# Xduino7_0.net
KiCad netlist of a schematic drawn in EAGLE
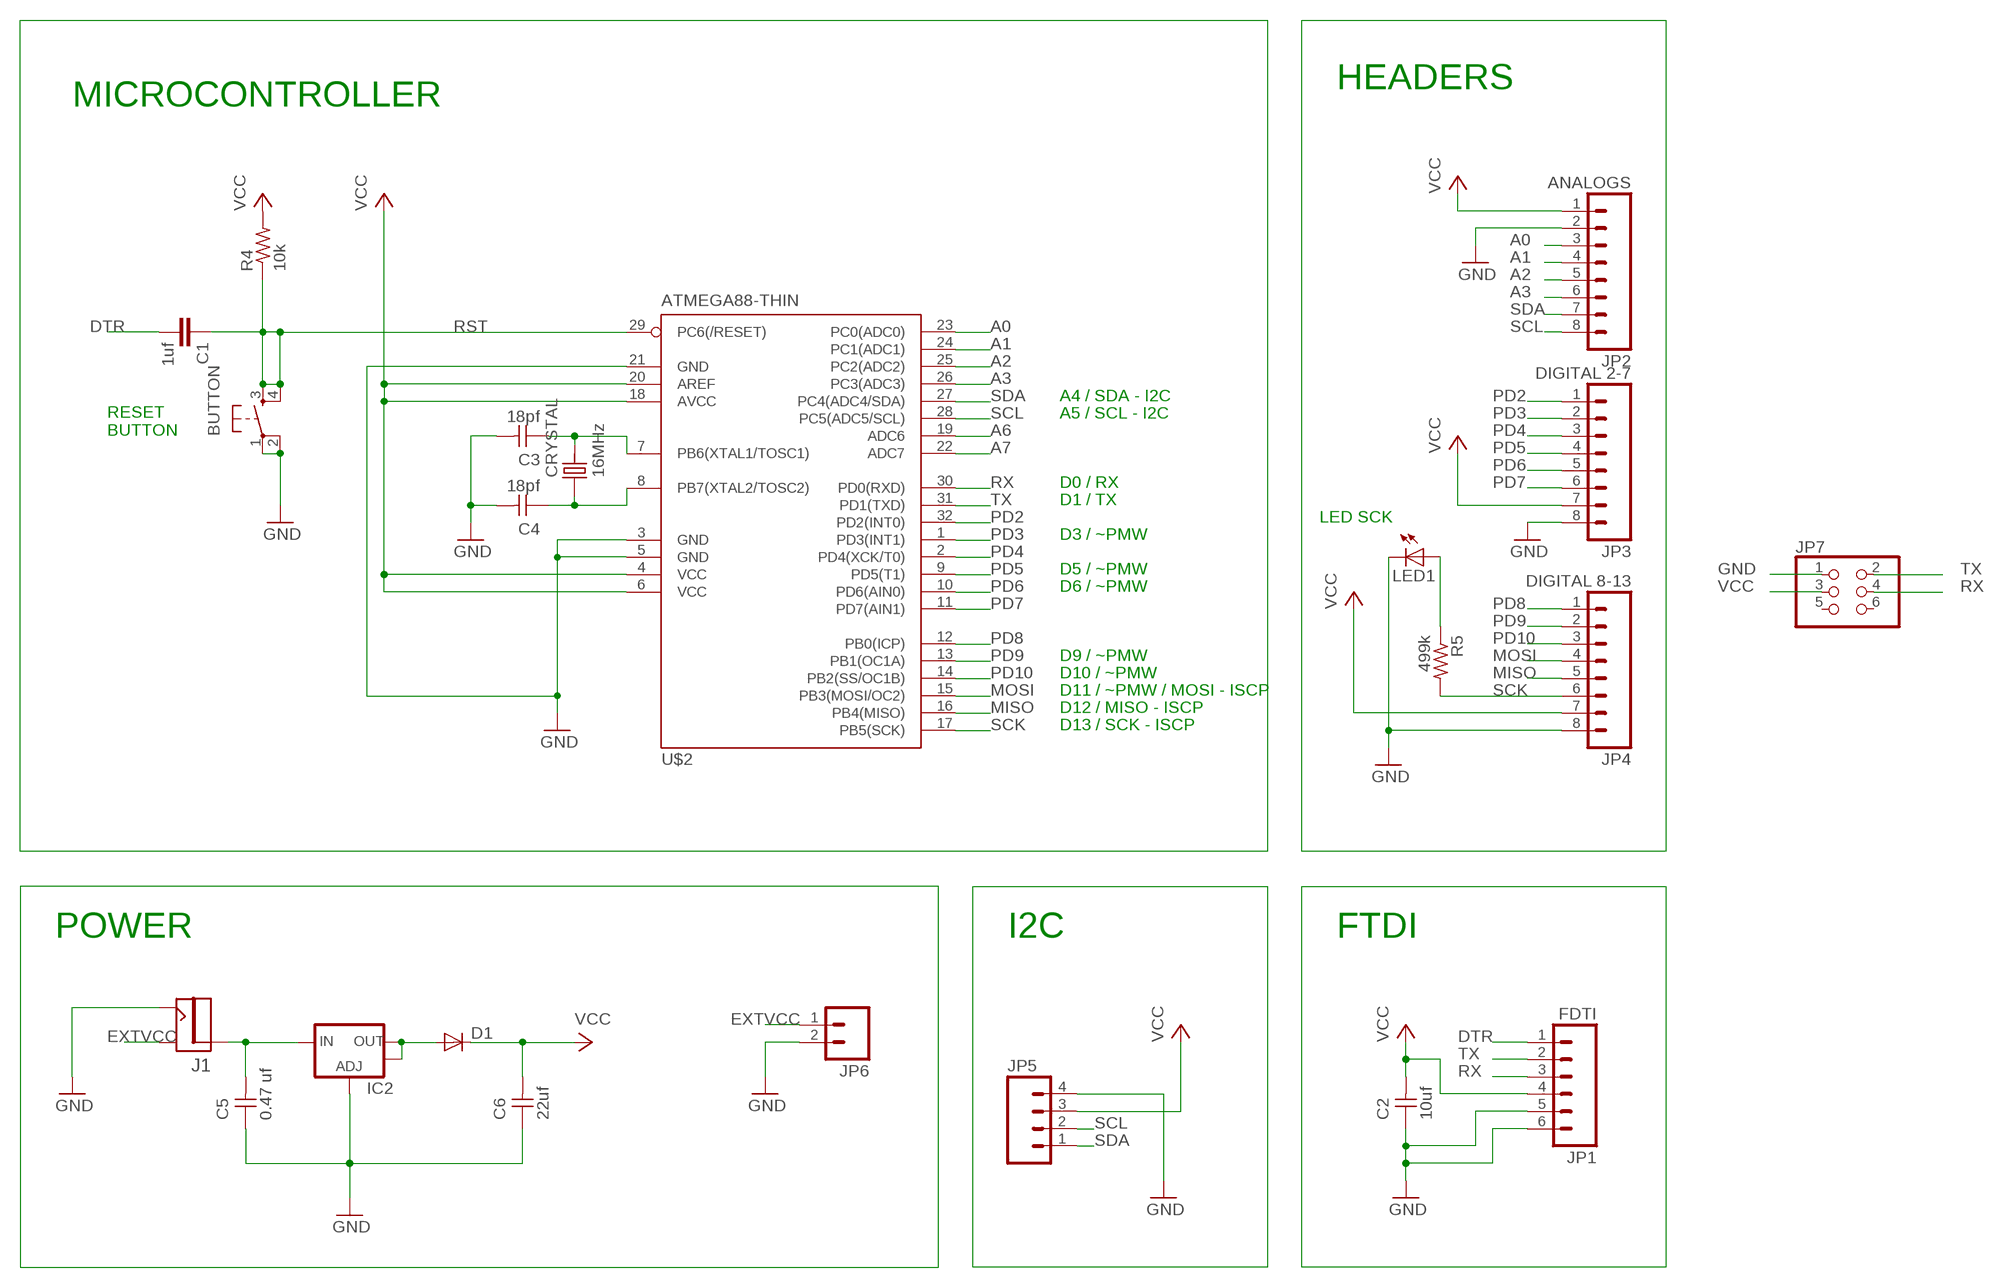
[diagram p0: schematic, sheet 1]

(export (version "E")
  (design (tool "Eeschema 10.0.6"))
  (components
    (comp (ref "BUTTON")
      (value "6MM_SWITCH6MM_SWITCH")
      (footprint "eagle-import:6MM_SWITCH")
      (libsource (lib "eagle-import") (part "6MM_SWITCH6MM_SWITCH"))
    )
    (comp (ref "C1")
      (value "1uf")
      (footprint "eagle-import:1206")
      (libsource (lib "eagle-import") (part "CAP1206"))
    )
    (comp (ref "C2")
      (value "10uf")
      (footprint "eagle-import:1206")
      (libsource (lib "eagle-import") (part "UNPOLARIZED_CAPACITOR1206"))
    )
    (comp (ref "C3")
      (value "18pf")
      (footprint "eagle-import:1206")
      (libsource (lib "eagle-import") (part "UNPOLARIZED_CAPACITOR1206"))
    )
    (comp (ref "C4")
      (value "18pf")
      (footprint "eagle-import:1206")
      (libsource (lib "eagle-import") (part "UNPOLARIZED_CAPACITOR1206"))
    )
    (comp (ref "C5")
      (value "0.47 uf")
      (footprint "eagle-import:1206")
      (libsource (lib "eagle-import") (part "UNPOLARIZED_CAPACITOR1206"))
    )
    (comp (ref "C6")
      (value "22uf")
      (footprint "eagle-import:1206")
      (libsource (lib "eagle-import") (part "UNPOLARIZED_CAPACITOR1206"))
    )
    (comp (ref "CRYSTAL")
      (value "16MHz")
      (footprint "eagle-import:CS10")
      (libsource (lib "eagle-import") (part "CRYSTALCS10"))
    )
    (comp (ref "D1")
      (value "DIODESOD123")
      (footprint "eagle-import:SOD123")
      (libsource (lib "eagle-import") (part "DIODESOD123"))
    )
    (comp (ref "IC2")
      (value "V_REG_LM1117SOT223")
      (footprint "eagle-import:SOT223")
      (libsource (lib "eagle-import") (part "V_REG_LM1117SOT223"))
    )
    (comp (ref "J1")
      (value "JACK.65MM")
      (footprint "eagle-import:JACK_.65MM")
      (libsource (lib "eagle-import") (part "JACK.65MM"))
    )
    (comp (ref "JP1")
      (value "FDTI")
      (footprint "eagle-import:1X06-SMD_EDGE")
      (libsource (lib "eagle-import") (part "M061X06-SMD_EDGE_FEMALE"))
    )
    (comp (ref "JP2")
      (value "ANALOGS")
      (footprint "eagle-import:1X08")
      (libsource (lib "eagle-import") (part "M08"))
    )
    (comp (ref "JP3")
      (value "DIGITAL 2-7")
      (footprint "eagle-import:1X08")
      (libsource (lib "eagle-import") (part "M08"))
    )
    (comp (ref "JP4")
      (value "DIGITAL 8-13")
      (footprint "eagle-import:1X08")
      (libsource (lib "eagle-import") (part "M08"))
    )
    (comp (ref "JP5")
      (value "M04PTH")
      (footprint "eagle-import:1X04")
      (libsource (lib "eagle-import") (part "M04PTH"))
    )
    (comp (ref "JP6")
      (value "M02PTH")
      (footprint "eagle-import:1X02")
      (libsource (lib "eagle-import") (part "M02PTH"))
    )
    (comp (ref "JP7")
      (value "PINHD-2X3-SMD")
      (footprint "eagle-import:2X03SMD")
      (libsource (lib "eagle-import") (part "PINHD-2X3-SMD"))
    )
    (comp (ref "LED1")
      (value "LED1206")
      (footprint "eagle-import:1206")
      (libsource (lib "eagle-import") (part "LED1206"))
    )
    (comp (ref "R4")
      (value "10k")
      (footprint "eagle-import:1206")
      (libsource (lib "eagle-import") (part "RESISTOR1206"))
    )
    (comp (ref "R5")
      (value "499k")
      (footprint "eagle-import:1206")
      (libsource (lib "eagle-import") (part "01_ng_RESISTOR1206"))
    )
    (comp (ref "U$2")
      (value "ATMEGA88-THIN")
      (footprint "eagle-import:TQFP32-08THIN")
      (libsource (lib "eagle-import") (part "ATMEGA88-THIN"))
    )
  )
  (nets
    (net (code "1") (name "/A0") (class "Default")
      (node (ref "JP2") (pin "3") (pinfunction "3_3") (pintype "passive"))
      (node (ref "U$2") (pin "23") (pinfunction "PC0(ADC0)_23") (pintype "bidirectional"))
    )
    (net (code "2") (name "/A1") (class "Default")
      (node (ref "JP2") (pin "4") (pinfunction "4_4") (pintype "passive"))
      (node (ref "U$2") (pin "24") (pinfunction "PC1(ADC1)_24") (pintype "bidirectional"))
    )
    (net (code "3") (name "/A2") (class "Default")
      (node (ref "JP2") (pin "5") (pinfunction "5_5") (pintype "passive"))
      (node (ref "U$2") (pin "25") (pinfunction "PC2(ADC2)_25") (pintype "bidirectional"))
    )
    (net (code "4") (name "/A3") (class "Default")
      (node (ref "JP2") (pin "6") (pinfunction "6_6") (pintype "passive"))
      (node (ref "U$2") (pin "26") (pinfunction "PC3(ADC3)_26") (pintype "bidirectional"))
    )
    (net (code "5") (name "/A6") (class "Default")
      (node (ref "U$2") (pin "19") (pinfunction "ADC6_19") (pintype "bidirectional"))
    )
    (net (code "6") (name "/A7") (class "Default")
      (node (ref "U$2") (pin "22") (pinfunction "ADC7_22") (pintype "bidirectional"))
    )
    (net (code "7") (name "/DTR") (class "Default")
      (node (ref "C1") (pin "2") (pinfunction "2_2") (pintype "passive"))
      (node (ref "JP1") (pin "1") (pinfunction "1_1") (pintype "passive"))
    )
    (net (code "8") (name "/EXTVCC") (class "Default")
      (node (ref "J1") (pin "CONTACT") (pinfunction "SHUNT_CONTACT") (pintype "bidirectional"))
      (node (ref "JP6") (pin "1") (pinfunction "1_1") (pintype "passive"))
    )
    (net (code "9") (name "/MISO") (class "Default")
      (node (ref "JP4") (pin "5") (pinfunction "5_5") (pintype "passive"))
      (node (ref "U$2") (pin "16") (pinfunction "PB4(MISO)_16") (pintype "bidirectional"))
    )
    (net (code "10") (name "/MOSI") (class "Default")
      (node (ref "JP4") (pin "4") (pinfunction "4_4") (pintype "passive"))
      (node (ref "U$2") (pin "15") (pinfunction "PB3(MOSI/OC2)_15") (pintype "bidirectional"))
    )
    (net (code "11") (name "/PD2") (class "Default")
      (node (ref "JP3") (pin "1") (pinfunction "1_1") (pintype "passive"))
      (node (ref "U$2") (pin "32") (pinfunction "PD2(INT0)_32") (pintype "bidirectional"))
    )
    (net (code "12") (name "/PD3") (class "Default")
      (node (ref "JP3") (pin "2") (pinfunction "2_2") (pintype "passive"))
      (node (ref "U$2") (pin "1") (pinfunction "PD3(INT1)_1") (pintype "bidirectional"))
    )
    (net (code "13") (name "/PD4") (class "Default")
      (node (ref "JP3") (pin "3") (pinfunction "3_3") (pintype "passive"))
      (node (ref "U$2") (pin "2") (pinfunction "PD4(XCK/T0)_2") (pintype "bidirectional"))
    )
    (net (code "14") (name "/PD5") (class "Default")
      (node (ref "JP3") (pin "4") (pinfunction "4_4") (pintype "passive"))
      (node (ref "U$2") (pin "9") (pinfunction "PD5(T1)_9") (pintype "bidirectional"))
    )
    (net (code "15") (name "/PD6") (class "Default")
      (node (ref "JP3") (pin "5") (pinfunction "5_5") (pintype "passive"))
      (node (ref "U$2") (pin "10") (pinfunction "PD6(AIN0)_10") (pintype "bidirectional"))
    )
    (net (code "16") (name "/PD7") (class "Default")
      (node (ref "JP3") (pin "6") (pinfunction "6_6") (pintype "passive"))
      (node (ref "U$2") (pin "11") (pinfunction "PD7(AIN1)_11") (pintype "bidirectional"))
    )
    (net (code "17") (name "/PD8") (class "Default")
      (node (ref "JP4") (pin "1") (pinfunction "1_1") (pintype "passive"))
      (node (ref "U$2") (pin "12") (pinfunction "PB0(ICP)_12") (pintype "bidirectional"))
    )
    (net (code "18") (name "/PD9") (class "Default")
      (node (ref "JP4") (pin "2") (pinfunction "2_2") (pintype "passive"))
      (node (ref "U$2") (pin "13") (pinfunction "PB1(OC1A)_13") (pintype "bidirectional"))
    )
    (net (code "19") (name "/PD10") (class "Default")
      (node (ref "JP4") (pin "3") (pinfunction "3_3") (pintype "passive"))
      (node (ref "U$2") (pin "14") (pinfunction "PB2(SS/OC1B)_14") (pintype "bidirectional"))
    )
    (net (code "20") (name "/RST") (class "Default")
      (node (ref "BUTTON") (pin "3") (pinfunction "S_3") (pintype "passive"))
      (node (ref "BUTTON") (pin "4") (pinfunction "S1_4") (pintype "passive"))
      (node (ref "C1") (pin "1") (pinfunction "1_1") (pintype "passive"))
      (node (ref "R4") (pin "1") (pinfunction "1_1") (pintype "passive"))
      (node (ref "U$2") (pin "29") (pinfunction "PC6(/RESET)_29") (pintype "bidirectional"))
    )
    (net (code "21") (name "/RX") (class "Default")
      (node (ref "JP1") (pin "3") (pinfunction "3_3") (pintype "passive"))
      (node (ref "JP7") (pin "4") (pinfunction "4_4") (pintype "passive"))
      (node (ref "U$2") (pin "30") (pinfunction "PD0(RXD)_30") (pintype "bidirectional"))
    )
    (net (code "22") (name "/SCK") (class "Default")
      (node (ref "JP4") (pin "6") (pinfunction "6_6") (pintype "passive"))
      (node (ref "R5") (pin "2") (pinfunction "2_2") (pintype "passive"))
      (node (ref "U$2") (pin "17") (pinfunction "PB5(SCK)_17") (pintype "bidirectional"))
    )
    (net (code "23") (name "/SCL") (class "Default")
      (node (ref "JP2") (pin "8") (pinfunction "8_8") (pintype "passive"))
      (node (ref "JP5") (pin "2") (pinfunction "2_2") (pintype "passive"))
      (node (ref "U$2") (pin "28") (pinfunction "PC5(ADC5/SCL)_28") (pintype "bidirectional"))
    )
    (net (code "24") (name "/SDA") (class "Default")
      (node (ref "JP2") (pin "7") (pinfunction "7_7") (pintype "passive"))
      (node (ref "JP5") (pin "1") (pinfunction "1_1") (pintype "passive"))
      (node (ref "U$2") (pin "27") (pinfunction "PC4(ADC4/SDA)_27") (pintype "bidirectional"))
    )
    (net (code "25") (name "/TX") (class "Default")
      (node (ref "JP1") (pin "2") (pinfunction "2_2") (pintype "passive"))
      (node (ref "JP7") (pin "2") (pinfunction "2_2") (pintype "passive"))
      (node (ref "U$2") (pin "31") (pinfunction "PD1(TXD)_31") (pintype "bidirectional"))
    )
    (net (code "26") (name "GND") (class "Default")
      (node (ref "BUTTON") (pin "1") (pinfunction "P_1") (pintype "passive"))
      (node (ref "BUTTON") (pin "2") (pinfunction "P1_2") (pintype "passive"))
      (node (ref "C2") (pin "1") (pinfunction "1_1") (pintype "passive"))
      (node (ref "C3") (pin "2") (pinfunction "2_2") (pintype "passive"))
      (node (ref "C4") (pin "2") (pinfunction "2_2") (pintype "passive"))
      (node (ref "C5") (pin "1") (pinfunction "1_1") (pintype "passive"))
      (node (ref "C6") (pin "1") (pinfunction "1_1") (pintype "passive"))
      (node (ref "IC2") (pin "1") (pinfunction "ADJ_1") (pintype "input"))
      (node (ref "J1") (pin "SHUNT") (pinfunction "CONTACT_SHUNT") (pintype "bidirectional"))
      (node (ref "JP1") (pin "5") (pinfunction "5_5") (pintype "passive"))
      (node (ref "JP1") (pin "6") (pinfunction "6_6") (pintype "passive"))
      (node (ref "JP2") (pin "2") (pinfunction "2_2") (pintype "passive"))
      (node (ref "JP3") (pin "8") (pinfunction "8_8") (pintype "passive"))
      (node (ref "JP4") (pin "8") (pinfunction "8_8") (pintype "passive"))
      (node (ref "JP5") (pin "4") (pinfunction "4_4") (pintype "passive"))
      (node (ref "JP6") (pin "2") (pinfunction "2_2") (pintype "passive"))
      (node (ref "JP7") (pin "1") (pinfunction "1_1") (pintype "passive"))
      (node (ref "LED1") (pin "2") (pinfunction "C_2") (pintype "passive"))
      (node (ref "U$2") (pin "21") (pinfunction "GND_21") (pintype "power_in"))
      (node (ref "U$2") (pin "3") (pinfunction "GND_3") (pintype "power_in"))
      (node (ref "U$2") (pin "5") (pinfunction "GND_5") (pintype "power_in"))
    )
    (net (code "27") (name "Net-(CRYSTAL-1)") (class "Default")
      (node (ref "C4") (pin "1") (pinfunction "1_1") (pintype "passive"))
      (node (ref "CRYSTAL") (pin "P$1") (pinfunction "1_P$1") (pintype "passive"))
      (node (ref "U$2") (pin "8") (pinfunction "PB7(XTAL2/TOSC2)_8") (pintype "bidirectional"))
    )
    (net (code "28") (name "Net-(CRYSTAL-2)") (class "Default")
      (node (ref "C3") (pin "1") (pinfunction "1_1") (pintype "passive"))
      (node (ref "CRYSTAL") (pin "P$2") (pinfunction "2_P$2") (pintype "passive"))
      (node (ref "U$2") (pin "7") (pinfunction "PB6(XTAL1/TOSC1)_7") (pintype "bidirectional"))
    )
    (net (code "29") (name "Net-(D1-A)") (class "Default")
      (node (ref "D1") (pin "ANODE") (pinfunction "A_ANODE") (pintype "passive"))
      (node (ref "IC2") (pin "2") (pinfunction "OUT_2") (pintype "output"))
      (node (ref "IC2") (pin "4") (pinfunction "OUT_4") (pintype "output"))
    )
    (net (code "30") (name "Net-(IC2-IN)") (class "Default")
      (node (ref "C5") (pin "2") (pinfunction "2_2") (pintype "passive"))
      (node (ref "IC2") (pin "3") (pinfunction "IN_3") (pintype "input"))
      (node (ref "J1") (pin "PIN") (pinfunction "PIN_PIN") (pintype "bidirectional"))
    )
    (net (code "31") (name "Net-(LED1-A)") (class "Default")
      (node (ref "LED1") (pin "1") (pinfunction "A_1") (pintype "passive"))
      (node (ref "R5") (pin "1") (pinfunction "1_1") (pintype "passive"))
    )
    (net (code "32") (name "VCC") (class "Default")
      (node (ref "C2") (pin "2") (pinfunction "2_2") (pintype "passive"))
      (node (ref "C6") (pin "2") (pinfunction "2_2") (pintype "passive"))
      (node (ref "D1") (pin "CATHODE") (pinfunction "C_CATHODE") (pintype "passive"))
      (node (ref "JP1") (pin "4") (pinfunction "4_4") (pintype "passive"))
      (node (ref "JP2") (pin "1") (pinfunction "1_1") (pintype "passive"))
      (node (ref "JP3") (pin "7") (pinfunction "7_7") (pintype "passive"))
      (node (ref "JP4") (pin "7") (pinfunction "7_7") (pintype "passive"))
      (node (ref "JP5") (pin "3") (pinfunction "3_3") (pintype "passive"))
      (node (ref "JP7") (pin "3") (pinfunction "3_3") (pintype "passive"))
      (node (ref "R4") (pin "2") (pinfunction "2_2") (pintype "passive"))
      (node (ref "U$2") (pin "18") (pinfunction "AVCC_18") (pintype "power_in"))
      (node (ref "U$2") (pin "20") (pinfunction "AREF_20") (pintype "passive"))
      (node (ref "U$2") (pin "4") (pinfunction "VCC_4") (pintype "power_in"))
      (node (ref "U$2") (pin "6") (pinfunction "VCC_6") (pintype "power_in"))
    )
    (net (code "33") (name "unconnected-(JP7-Pad5)") (class "Default")
      (node (ref "JP7") (pin "5") (pinfunction "5_5") (pintype "passive"))
    )
    (net (code "34") (name "unconnected-(JP7-Pad6)") (class "Default")
      (node (ref "JP7") (pin "6") (pinfunction "6_6") (pintype "passive"))
    )
  )
)
